# Sheet1.net
KiCad netlist of a schematic drawn in Altium Designer
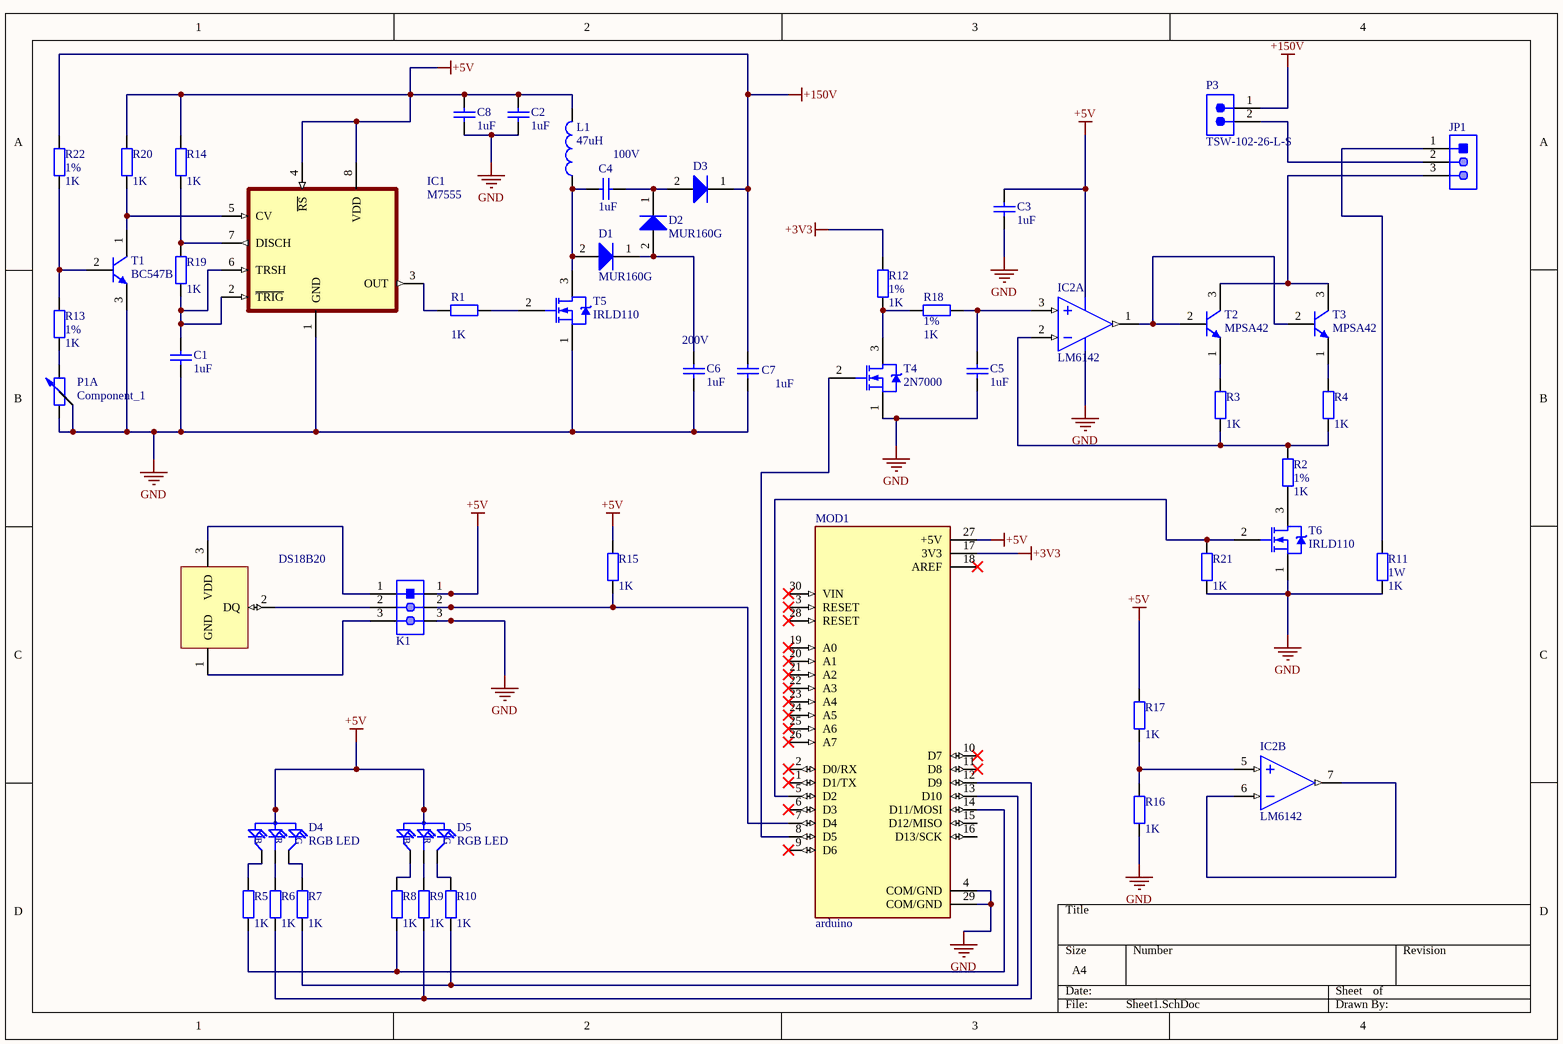
[diagram p0: Sheet1.SchDoc]

(export (version "E")
  (design (tool "Eeschema 10.0.6"))
  (components
    (comp (ref "C1")
      (value "1uF")
      (footprint "RAD-0.3")
      (description "Capacitor")
      (fields (field (name "Comment") "Cap") (field (name "PUBLISHER") "Altium Limited"))
      (libsource (lib "SchemaLIB") (part "Capacitor"))
    )
    (comp (ref "C2")
      (value "1uF")
      (footprint "RAD-0.3")
      (description "Capacitor")
      (fields (field (name "Comment") "Cap") (field (name "PUBLISHER") "Altium Limited"))
      (libsource (lib "SchemaLIB") (part "Capacitor"))
    )
    (comp (ref "C3")
      (value "1uF")
      (footprint "RAD-0.3")
      (description "Capacitor")
      (fields (field (name "Comment") "Cap") (field (name "PUBLISHER") "Altium Limited"))
      (libsource (lib "SchemaLIB") (part "Capacitor"))
    )
    (comp (ref "C4")
      (value "100V")
      (footprint "Ceramic Capacitor")
      (description "Capacitor")
      (fields (field (name "ALTIUM_VALUE") "1uF") (field (name "PUBLISHER") "Altium Limited"))
      (libsource (lib "SchemaLIB") (part "Capacitor"))
    )
    (comp (ref "C5")
      (value "1uF")
      (footprint "RAD-0.3")
      (description "Capacitor")
      (fields (field (name "Comment") "Cap") (field (name "PUBLISHER") "Altium Limited"))
      (libsource (lib "SchemaLIB") (part "Capacitor"))
    )
    (comp (ref "C6")
      (value "200V")
      (footprint "electrolytic capacitor 2.2uf")
      (description "Capacitor")
      (fields (field (name "ALTIUM_VALUE") "1uF") (field (name "PUBLISHER") "Altium Limited"))
      (libsource (lib "Nixie-thermometer_SchemaLIB") (part "C1uF"))
    )
    (comp (ref "C7")
      (value "1uF")
      (footprint "electrolytic capacitor 2.2uf")
      (description "Capacitor")
      (fields (field (name "Comment") "200V") (field (name "PUBLISHER") "Altium Limited"))
      (libsource (lib "Nixie-thermometer_SchemaLIB") (part "C1uF"))
    )
    (comp (ref "C8")
      (value "1uF")
      (footprint "RAD-0.3")
      (description "Capacitor")
      (fields (field (name "Comment") "Cap") (field (name "PUBLISHER") "Altium Limited"))
      (libsource (lib "SchemaLIB") (part "Capacitor"))
    )
    (comp (ref "D1")
      (value "MUR160G")
      (footprint "MUR160G")
      (description "Diode")
      (fields (field (name "MANUFACTURER") "ON Semiconductor"))
      (libsource (lib "SchemaLIB") (part "Diode"))
    )
    (comp (ref "D2")
      (value "MUR160G")
      (footprint "MUR160G")
      (description "Diode")
      (fields (field (name "MANUFACTURER") "ON Semiconductor"))
      (libsource (lib "SchemaLIB") (part "Diode"))
    )
    (comp (ref "D3")
      (value "MUR160G")
      (footprint "MUR160G")
      (description "Diode")
      (fields (field (name "MANUFACTURER") "ON Semiconductor"))
      (libsource (lib "SchemaLIB") (part "Diode"))
    )
    (comp (ref "D4") (value "RGB LED") (description "RGB Led") (libsource (lib "SchemaLIB") (part "RGB LED")))
    (comp (ref "D5") (value "RGB LED") (description "RGB Led") (libsource (lib "SchemaLIB") (part "RGB LED")))
    (comp (ref "DS18B20")
      (value "DS18B20+")
      (footprint "Q3+1")
      (description "IC")
      (fields (field (name "MANUFACTURER") "Maxim"))
      (libsource (lib "SchemaLIB") (part "DS18B20+"))
    )
    (comp (ref "IC1")
      (value "M7555")
      (footprint "M7555")
      (description "IC")
      (fields (field (name "MF") "Renesas Electronics") (field (name "MP") "ICM7555CBAZ"))
      (libsource (lib "SchemaLIB") (part "M7555"))
    )
    (comp (ref "IC2")
      (value "LM6142")
      (footprint "LM6142")
      (description "IC")
      (fields
        (field (name "MANUFACTURER") "TI National Semiconductor")
        (field (name "MANUFACTURER PART NUMBER") "LM6142AIM")
      )
      (libsource (lib "SchemaLIB") (part "LM6412"))
    )
    (comp (ref "JP1")
      (value "22-28-4033")
      (footprint "MOLX-22-28-4033_V")
      (description "Male Header, Pitch 2.54 mm, 1 x 3 Position, Height 8.38 mm, Tail Length 3.18 mm, RoHS, Bulk")
      (fields (field (name "MANUFACTURER") "Molex"))
      (libsource (lib "Altium Content Vault") (part "CN-1P-M-R3"))
    )
    (comp (ref "K1")
      (value "61900319521")
      (footprint "K1")
      (description "Connector")
      (fields (field (name "MANUFACTURER") "Wurth Electronics") (field (name "PUBLISHER") "WurthElektronik"))
      (libsource (lib "Nixie-thermometer_SchemaLIB") (part "K1"))
    )
    (comp (ref "L1")
      (value "47uH")
      (footprint "ELC08D470E")
      (description "Inductor")
      (fields (field (name "PUBLISHER") "Altium Limited"))
      (libsource (lib "SchemaLIB") (part "Inductor"))
    )
    (comp (ref "MOD1")
      (value "arduino")
      (description "Arduino nano")
      (libsource (lib "SchemaLIB") (part "arduino"))
    )
    (comp (ref "P1") (value "Component_1") (libsource (lib "pot") (part "Component_1")))
    (comp (ref "P3")
      (value "TSW-102-26-L-S")
      (footprint "SMTC-TSW-102-26-XX-S")
      (description "0.025\" SQ Post Header, Through-hole, Vertical, -55 to 125 degC, 2.54 mm Pitch, 2-Pin, Male, RoHS")
      (fields (field (name "MANUFACTURER") "Samtec"))
      (libsource (lib "Altium Content Vault") (part "SMTC-TSW-102-X-X-S-X"))
    )
    (comp (ref "R1")
      (value "1K")
      (footprint "Resistor")
      (description "Resistor")
      (fields (field (name "Comment") "1%") (field (name "PUBLISHER") "Altium Limited"))
      (libsource (lib "") (part "Resistor_1"))
    )
    (comp (ref "R2")
      (value "1%")
      (footprint "SMD resistor")
      (description "Resistor")
      (fields (field (name "ALTIUM_VALUE") "1K") (field (name "PUBLISHER") "Altium Limited"))
      (libsource (lib "Miscellaneous Devices") (part "Res2"))
    )
    (comp (ref "R3")
      (value "1K")
      (footprint "SMD resistor")
      (description "Resistor")
      (fields (field (name "Comment") "Res2") (field (name "PUBLISHER") "Altium Limited"))
      (libsource (lib "Miscellaneous Devices") (part "Res2"))
    )
    (comp (ref "R4")
      (value "1K")
      (footprint "SMD resistor")
      (description "Resistor")
      (fields (field (name "Comment") "Res2") (field (name "PUBLISHER") "Altium Limited"))
      (libsource (lib "Miscellaneous Devices") (part "Res2"))
    )
    (comp (ref "R5")
      (value "1K")
      (footprint "Resistor")
      (description "Resistor")
      (fields (field (name "Comment") "Res2") (field (name "PUBLISHER") "Altium Limited"))
      (libsource (lib "Miscellaneous Devices") (part "Res2"))
    )
    (comp (ref "R6")
      (value "1K")
      (footprint "Resistor")
      (description "Resistor")
      (fields (field (name "Comment") "Res2") (field (name "PUBLISHER") "Altium Limited"))
      (libsource (lib "Miscellaneous Devices") (part "Res2"))
    )
    (comp (ref "R7")
      (value "1K")
      (footprint "Resistor")
      (description "Resistor")
      (fields (field (name "Comment") "Res2") (field (name "PUBLISHER") "Altium Limited"))
      (libsource (lib "Miscellaneous Devices") (part "Res2"))
    )
    (comp (ref "R8")
      (value "1K")
      (footprint "Resistor")
      (description "Resistor")
      (fields (field (name "Comment") "Res2") (field (name "PUBLISHER") "Altium Limited"))
      (libsource (lib "Miscellaneous Devices") (part "Res2"))
    )
    (comp (ref "R9")
      (value "1K")
      (footprint "Resistor")
      (description "Resistor")
      (fields (field (name "Comment") "Res2") (field (name "PUBLISHER") "Altium Limited"))
      (libsource (lib "Miscellaneous Devices") (part "Res2"))
    )
    (comp (ref "R10")
      (value "1K")
      (footprint "Resistor")
      (description "Resistor")
      (fields (field (name "Comment") "Res2") (field (name "PUBLISHER") "Altium Limited"))
      (libsource (lib "Miscellaneous Devices") (part "Res2"))
    )
    (comp (ref "R11")
      (value "1W")
      (footprint "RESISTOR 1W")
      (description "Resistor")
      (fields (field (name "ALTIUM_VALUE") "1K") (field (name "PUBLISHER") "Altium Limited"))
      (libsource (lib "SchemaLIB") (part "Resistor"))
    )
    (comp (ref "R12")
      (value "1%")
      (footprint "SMD resistor")
      (description "Resistor")
      (fields (field (name "ALTIUM_VALUE") "1K") (field (name "PUBLISHER") "Altium Limited"))
      (libsource (lib "SchemaLIB") (part "Resistor"))
    )
    (comp (ref "R13")
      (value "1%")
      (footprint "Resistor")
      (description "Resistor")
      (fields (field (name "ALTIUM_VALUE") "1K") (field (name "PUBLISHER") "Altium Limited"))
      (libsource (lib "Miscellaneous Devices") (part "Res2"))
    )
    (comp (ref "R14")
      (value "1K")
      (footprint "Resistor")
      (description "Resistor")
      (fields (field (name "Comment") "Res2") (field (name "PUBLISHER") "Altium Limited"))
      (libsource (lib "Miscellaneous Devices") (part "Res2"))
    )
    (comp (ref "R15")
      (value "1K")
      (footprint "Resistor")
      (description "Resistor")
      (fields (field (name "Comment") "Res2") (field (name "PUBLISHER") "Altium Limited"))
      (libsource (lib "Miscellaneous Devices") (part "Res2"))
    )
    (comp (ref "R16")
      (value "1K")
      (footprint "SMD resistor")
      (description "Resistor")
      (fields (field (name "Comment") "1%") (field (name "PUBLISHER") "Altium Limited"))
      (libsource (lib "SchemaLIB") (part "Resistor"))
    )
    (comp (ref "R17")
      (value "1K")
      (footprint "SMD resistor")
      (description "Resistor")
      (fields (field (name "Comment") "1%") (field (name "PUBLISHER") "Altium Limited"))
      (libsource (lib "SchemaLIB") (part "Resistor"))
    )
    (comp (ref "R18")
      (value "1%")
      (footprint "SMD resistor")
      (description "Resistor")
      (fields (field (name "ALTIUM_VALUE") "1K") (field (name "PUBLISHER") "Altium Limited"))
      (libsource (lib "") (part "Resistor_1"))
    )
    (comp (ref "R19")
      (value "1K")
      (footprint "Resistor")
      (description "Resistor")
      (fields (field (name "Comment") "Res2") (field (name "PUBLISHER") "Altium Limited"))
      (libsource (lib "Miscellaneous Devices") (part "Res2"))
    )
    (comp (ref "R20")
      (value "1K")
      (footprint "Resistor")
      (description "Resistor")
      (fields (field (name "Comment") "Res2") (field (name "PUBLISHER") "Altium Limited"))
      (libsource (lib "Miscellaneous Devices") (part "Res2"))
    )
    (comp (ref "R21")
      (value "1K")
      (footprint "SMD resistor")
      (description "Resistor")
      (fields (field (name "Comment") "1%") (field (name "PUBLISHER") "Altium Limited"))
      (libsource (lib "SchemaLIB") (part "Resistor"))
    )
    (comp (ref "R22")
      (value "1%")
      (footprint "Resistor")
      (description "Resistor")
      (fields (field (name "ALTIUM_VALUE") "1K") (field (name "PUBLISHER") "Altium Limited"))
      (libsource (lib "SchemaLIB") (part "Resistor"))
    )
    (comp (ref "T1")
      (value "BC547B")
      (footprint "BC547B")
      (description "Transistor")
      (fields (field (name "MANUFACTURER") "ON Semiconductor / Fairchild"))
      (libsource (lib "SchemaLIB") (part "BC547B"))
    )
    (comp (ref "T2")
      (value "MPSA42")
      (footprint "BC547B")
      (description "Transistor")
      (fields (field (name "MANUFACTURER") "ON Semiconductor / Fairchild"))
      (libsource (lib "SchemaLIB") (part "MPSA42"))
    )
    (comp (ref "T3")
      (value "MPSA42")
      (footprint "BC547B")
      (description "Transistor")
      (fields (field (name "MANUFACTURER") "ON Semiconductor / Fairchild"))
      (libsource (lib "SchemaLIB") (part "MPSA42"))
    )
    (comp (ref "T4")
      (value "2N7000")
      (footprint "BC547B")
      (description "Transistor")
      (fields (field (name "MANUFACTURER") "ON Semiconductor / Fairchild"))
      (libsource (lib "SchemaLIB") (part "IC2N7000"))
    )
    (comp (ref "T5")
      (value "IRLD110")
      (description "Transistor")
      (libsource (lib "SchemaLIB") (part "IRLD110"))
    )
    (comp (ref "T6")
      (value "IRLD110")
      (description "Transistor")
      (libsource (lib "SchemaLIB") (part "IRLD110"))
    )
  )
  (nets
    (net (code "1") (name "+3V3") (class "Default")
      (node (ref "MOD1") (pin "17") (pinfunction "3V3_17") (pintype "power_in"))
      (node (ref "R12") (pin "2") (pinfunction "2_2") (pintype "passive"))
    )
    (net (code "2") (name "+5V") (class "Default")
      (node (ref "C2") (pin "2") (pinfunction "2_2") (pintype "passive"))
      (node (ref "C3") (pin "2") (pinfunction "2_2") (pintype "passive"))
      (node (ref "C8") (pin "2") (pinfunction "2_2") (pintype "passive"))
      (node (ref "D4") (pin "C") (pinfunction "POS_C") (pintype "bidirectional"))
      (node (ref "D5") (pin "C") (pinfunction "POS_C") (pintype "bidirectional"))
      (node (ref "IC1") (pin "4") (pinfunction "~{RS}_4") (pintype "input"))
      (node (ref "IC1") (pin "8") (pinfunction "VDD_8") (pintype "power_in"))
      (node (ref "K1") (pin "1") (pinfunction "1_1") (pintype "passive"))
      (node (ref "L1") (pin "2") (pinfunction "2_2") (pintype "passive"))
      (node (ref "MOD1") (pin "27") (pinfunction "+5V_27") (pintype "power_in"))
      (node (ref "R14") (pin "2") (pinfunction "2_2") (pintype "passive"))
      (node (ref "R15") (pin "2") (pinfunction "2_2") (pintype "passive"))
      (node (ref "R17") (pin "2") (pinfunction "2_2") (pintype "passive"))
      (node (ref "R20") (pin "2") (pinfunction "2_2") (pintype "passive"))
    )
    (net (code "3") (name "+150V") (class "Default")
      (node (ref "C7") (pin "2") (pinfunction "2_2") (pintype "passive"))
      (node (ref "D3") (pin "1") (pinfunction "K_1") (pintype "passive"))
      (node (ref "P3") (pin "1") (pinfunction "1_1") (pintype "passive"))
      (node (ref "R22") (pin "2") (pinfunction "2_2") (pintype "passive"))
    )
    (net (code "4") (name "GND") (class "Default")
      (node (ref "C1") (pin "1") (pinfunction "1_1") (pintype "passive"))
      (node (ref "C2") (pin "1") (pinfunction "1_1") (pintype "passive"))
      (node (ref "C3") (pin "1") (pinfunction "1_1") (pintype "passive"))
      (node (ref "C5") (pin "1") (pinfunction "1_1") (pintype "passive"))
      (node (ref "C6") (pin "1") (pinfunction "1_1") (pintype "passive"))
      (node (ref "C7") (pin "1") (pinfunction "1_1") (pintype "passive"))
      (node (ref "C8") (pin "1") (pinfunction "1_1") (pintype "passive"))
      (node (ref "IC1") (pin "1") (pinfunction "GND_1") (pintype "passive"))
      (node (ref "K1") (pin "3") (pinfunction "3_3") (pintype "passive"))
      (node (ref "MOD1") (pin "29") (pinfunction "COM/GND_29") (pintype "power_in"))
      (node (ref "MOD1") (pin "4") (pinfunction "COM/GND_4") (pintype "power_in"))
      (node (ref "P1") (pin "1") (pinfunction "1_1") (pintype "passive"))
      (node (ref "P1") (pin "3") (pinfunction "3_3") (pintype "passive"))
      (node (ref "R11") (pin "1") (pinfunction "1_1") (pintype "passive"))
      (node (ref "R16") (pin "1") (pinfunction "1_1") (pintype "passive"))
      (node (ref "R21") (pin "1") (pinfunction "1_1") (pintype "passive"))
      (node (ref "T1") (pin "3") (pinfunction "E_3") (pintype "passive"))
      (node (ref "T4") (pin "1") (pinfunction "S_1") (pintype "passive"))
      (node (ref "T5") (pin "1") (pinfunction "S_1") (pintype "passive"))
      (node (ref "T6") (pin "1") (pinfunction "S_1") (pintype "passive"))
    )
    (net (code "5") (name "Net-(D1-A)") (class "Default")
      (node (ref "C4") (pin "2") (pinfunction "2_2") (pintype "passive"))
      (node (ref "D1") (pin "2") (pinfunction "A_2") (pintype "passive"))
      (node (ref "L1") (pin "1") (pinfunction "1_1") (pintype "passive"))
      (node (ref "T5") (pin "3") (pinfunction "D_3") (pintype "passive"))
    )
    (net (code "6") (name "Net-(D1-K)") (class "Default")
      (node (ref "C6") (pin "2") (pinfunction "2_2") (pintype "passive"))
      (node (ref "D1") (pin "1") (pinfunction "K_1") (pintype "passive"))
      (node (ref "D2") (pin "2") (pinfunction "A_2") (pintype "passive"))
    )
    (net (code "7") (name "Net-(D2-K)") (class "Default")
      (node (ref "C4") (pin "1") (pinfunction "1_1") (pintype "passive"))
      (node (ref "D2") (pin "1") (pinfunction "K_1") (pintype "passive"))
      (node (ref "D3") (pin "2") (pinfunction "A_2") (pintype "passive"))
    )
    (net (code "8") (name "Net-(D4-PadB)") (class "Default")
      (node (ref "D4") (pin "B") (pinfunction "B_B") (pintype "bidirectional"))
      (node (ref "R5") (pin "2") (pinfunction "2_2") (pintype "passive"))
    )
    (net (code "9") (name "Net-(D4-PadG)") (class "Default")
      (node (ref "D4") (pin "G") (pinfunction "G_G") (pintype "bidirectional"))
      (node (ref "R7") (pin "2") (pinfunction "2_2") (pintype "passive"))
    )
    (net (code "10") (name "Net-(D4-PadR)") (class "Default")
      (node (ref "D4") (pin "R") (pinfunction "R_R") (pintype "bidirectional"))
      (node (ref "R6") (pin "2") (pinfunction "2_2") (pintype "passive"))
    )
    (net (code "11") (name "Net-(D5-PadB)") (class "Default")
      (node (ref "D5") (pin "B") (pinfunction "B_B") (pintype "bidirectional"))
      (node (ref "R8") (pin "2") (pinfunction "2_2") (pintype "passive"))
    )
    (net (code "12") (name "Net-(D5-PadG)") (class "Default")
      (node (ref "D5") (pin "G") (pinfunction "G_G") (pintype "bidirectional"))
      (node (ref "R10") (pin "2") (pinfunction "2_2") (pintype "passive"))
    )
    (net (code "13") (name "Net-(D5-PadR)") (class "Default")
      (node (ref "D5") (pin "R") (pinfunction "R_R") (pintype "bidirectional"))
      (node (ref "R9") (pin "2") (pinfunction "2_2") (pintype "passive"))
    )
    (net (code "14") (name "Net-(DS18B20-DQ)") (class "Default")
      (node (ref "DS18B20") (pin "2") (pinfunction "DQ_2") (pintype "bidirectional"))
      (node (ref "K1") (pin "2") (pinfunction "2_2") (pintype "passive"))
    )
    (net (code "15") (name "Net-(DS18B20-GND)") (class "Default")
      (node (ref "DS18B20") (pin "1") (pinfunction "GND_1") (pintype "power_in"))
      (node (ref "K1") (pin "3") (pinfunction "3_3") (pintype "passive"))
    )
    (net (code "16") (name "Net-(DS18B20-VDD)") (class "Default")
      (node (ref "DS18B20") (pin "3") (pinfunction "VDD_3") (pintype "power_in"))
      (node (ref "K1") (pin "1") (pinfunction "1_1") (pintype "passive"))
    )
    (net (code "17") (name "Net-(IC1-CV)") (class "Default")
      (node (ref "IC1") (pin "5") (pinfunction "CV_5") (pintype "input"))
      (node (ref "R20") (pin "1") (pinfunction "1_1") (pintype "passive"))
      (node (ref "T1") (pin "1") (pinfunction "C_1") (pintype "passive"))
    )
    (net (code "18") (name "Net-(IC1-DISCH)") (class "Default")
      (node (ref "IC1") (pin "7") (pinfunction "DISCH_7") (pintype "output"))
      (node (ref "R14") (pin "1") (pinfunction "1_1") (pintype "passive"))
      (node (ref "R19") (pin "2") (pinfunction "2_2") (pintype "passive"))
    )
    (net (code "19") (name "Net-(IC1-OUT)") (class "Default")
      (node (ref "IC1") (pin "3") (pinfunction "OUT_3") (pintype "output"))
      (node (ref "R1") (pin "1") (pinfunction "1_1") (pintype "passive"))
    )
    (net (code "20") (name "Net-(IC1-TRSH)") (class "Default")
      (node (ref "C1") (pin "2") (pinfunction "2_2") (pintype "passive"))
      (node (ref "IC1") (pin "2") (pinfunction "~{TRIG}_2") (pintype "input"))
      (node (ref "IC1") (pin "6") (pinfunction "TRSH_6") (pintype "input"))
      (node (ref "R19") (pin "1") (pinfunction "1_1") (pintype "passive"))
    )
    (net (code "21") (name "Net-(IC2A-INA+)") (class "Default")
      (node (ref "C5") (pin "2") (pinfunction "2_2") (pintype "passive"))
      (node (ref "IC2") (pin "3") (pinfunction "INA+_3") (pintype "input"))
      (node (ref "R18") (pin "2") (pinfunction "2_2") (pintype "passive"))
    )
    (net (code "22") (name "Net-(IC2A-INA-)") (class "Default")
      (node (ref "IC2") (pin "2") (pinfunction "INA-_2") (pintype "input"))
      (node (ref "R2") (pin "2") (pinfunction "2_2") (pintype "passive"))
      (node (ref "R3") (pin "1") (pinfunction "1_1") (pintype "passive"))
      (node (ref "R4") (pin "1") (pinfunction "1_1") (pintype "passive"))
    )
    (net (code "23") (name "Net-(IC2A-OUTA)") (class "Default")
      (node (ref "IC2") (pin "1") (pinfunction "OUTA_1") (pintype "output"))
      (node (ref "T2") (pin "2") (pinfunction "B_2") (pintype "passive"))
      (node (ref "T3") (pin "2") (pinfunction "B_2") (pintype "passive"))
    )
    (net (code "24") (name "Net-(IC2B-INB+)") (class "Default")
      (node (ref "IC2") (pin "5") (pinfunction "INB+_5") (pintype "input"))
      (node (ref "R16") (pin "2") (pinfunction "2_2") (pintype "passive"))
      (node (ref "R17") (pin "1") (pinfunction "1_1") (pintype "passive"))
    )
    (net (code "25") (name "Net-(IC2B-INB-)") (class "Default")
      (node (ref "IC2") (pin "6") (pinfunction "INB-_6") (pintype "input"))
      (node (ref "IC2") (pin "7") (pinfunction "OUTB_7") (pintype "output"))
    )
    (net (code "26") (name "Net-(JP1-Pad1)") (class "Default")
      (node (ref "JP1") (pin "1") (pinfunction "1_1") (pintype "passive"))
      (node (ref "R11") (pin "2") (pinfunction "2_2") (pintype "passive"))
    )
    (net (code "27") (name "Net-(JP1-Pad2)") (class "Default")
      (node (ref "JP1") (pin "2") (pinfunction "2_2") (pintype "passive"))
      (node (ref "P3") (pin "2") (pinfunction "2_2") (pintype "passive"))
    )
    (net (code "28") (name "Net-(MOD1-D2)") (class "Default")
      (node (ref "MOD1") (pin "5") (pinfunction "D2_5") (pintype "bidirectional"))
      (node (ref "R21") (pin "2") (pinfunction "2_2") (pintype "passive"))
      (node (ref "T6") (pin "2") (pinfunction "G_2") (pintype "passive"))
    )
    (net (code "29") (name "Net-(MOD1-D4)") (class "Default")
      (node (ref "K1") (pin "2") (pinfunction "2_2") (pintype "passive"))
      (node (ref "MOD1") (pin "7") (pinfunction "D4_7") (pintype "bidirectional"))
      (node (ref "R15") (pin "1") (pinfunction "1_1") (pintype "passive"))
    )
    (net (code "30") (name "Net-(MOD1-D5)") (class "Default")
      (node (ref "MOD1") (pin "8") (pinfunction "D5_8") (pintype "bidirectional"))
      (node (ref "T4") (pin "2") (pinfunction "G_2") (pintype "passive"))
    )
    (net (code "31") (name "Net-(MOD1-D9)") (class "Default")
      (node (ref "MOD1") (pin "12") (pinfunction "D9_12") (pintype "bidirectional"))
      (node (ref "R6") (pin "1") (pinfunction "1_1") (pintype "passive"))
      (node (ref "R9") (pin "1") (pinfunction "1_1") (pintype "passive"))
    )
    (net (code "32") (name "Net-(MOD1-D10)") (class "Default")
      (node (ref "MOD1") (pin "13") (pinfunction "D10_13") (pintype "bidirectional"))
      (node (ref "R10") (pin "1") (pinfunction "1_1") (pintype "passive"))
      (node (ref "R7") (pin "1") (pinfunction "1_1") (pintype "passive"))
    )
    (net (code "33") (name "Net-(MOD1-D11{slash}MOSI)") (class "Default")
      (node (ref "MOD1") (pin "14") (pinfunction "D11/MOSI_14") (pintype "bidirectional"))
      (node (ref "R5") (pin "1") (pinfunction "1_1") (pintype "passive"))
      (node (ref "R8") (pin "1") (pinfunction "1_1") (pintype "passive"))
    )
    (net (code "34") (name "Net-(P1-Pad2)") (class "Default")
      (node (ref "P1") (pin "2") (pinfunction "2_2") (pintype "passive"))
      (node (ref "R13") (pin "1") (pinfunction "1_1") (pintype "passive"))
    )
    (net (code "35") (name "Net-(T1-B)") (class "Default")
      (node (ref "R13") (pin "2") (pinfunction "2_2") (pintype "passive"))
      (node (ref "R22") (pin "1") (pinfunction "1_1") (pintype "passive"))
      (node (ref "T1") (pin "2") (pinfunction "B_2") (pintype "passive"))
    )
    (net (code "36") (name "Net-(T2-C)") (class "Default")
      (node (ref "JP1") (pin "3") (pinfunction "3_3") (pintype "passive"))
      (node (ref "T2") (pin "3") (pinfunction "C_3") (pintype "passive"))
      (node (ref "T3") (pin "3") (pinfunction "C_3") (pintype "passive"))
    )
    (net (code "37") (name "Net-(T2-E)") (class "Default")
      (node (ref "R3") (pin "2") (pinfunction "2_2") (pintype "passive"))
      (node (ref "T2") (pin "1") (pinfunction "E_1") (pintype "passive"))
    )
    (net (code "38") (name "Net-(T3-E)") (class "Default")
      (node (ref "R4") (pin "2") (pinfunction "2_2") (pintype "passive"))
      (node (ref "T3") (pin "1") (pinfunction "E_1") (pintype "passive"))
    )
    (net (code "39") (name "Net-(T4-D)") (class "Default")
      (node (ref "R12") (pin "1") (pinfunction "1_1") (pintype "passive"))
      (node (ref "R18") (pin "1") (pinfunction "1_1") (pintype "passive"))
      (node (ref "T4") (pin "3") (pinfunction "D_3") (pintype "passive"))
    )
    (net (code "40") (name "Net-(T5-G)") (class "Default")
      (node (ref "R1") (pin "2") (pinfunction "2_2") (pintype "passive"))
      (node (ref "T5") (pin "2") (pinfunction "G_2") (pintype "passive"))
    )
    (net (code "41") (name "Net-(T6-D)") (class "Default")
      (node (ref "R2") (pin "1") (pinfunction "1_1") (pintype "passive"))
      (node (ref "T6") (pin "3") (pinfunction "D_3") (pintype "passive"))
    )
    (net (code "42") (name "unconnected-(MOD1-A0-Pad19)") (class "Default")
      (node (ref "MOD1") (pin "19") (pinfunction "A0_19") (pintype "input+no_connect"))
    )
    (net (code "43") (name "unconnected-(MOD1-A1-Pad20)") (class "Default")
      (node (ref "MOD1") (pin "20") (pinfunction "A1_20") (pintype "input+no_connect"))
    )
    (net (code "44") (name "unconnected-(MOD1-A2-Pad21)") (class "Default")
      (node (ref "MOD1") (pin "21") (pinfunction "A2_21") (pintype "input+no_connect"))
    )
    (net (code "45") (name "unconnected-(MOD1-A3-Pad22)") (class "Default")
      (node (ref "MOD1") (pin "22") (pinfunction "A3_22") (pintype "input+no_connect"))
    )
    (net (code "46") (name "unconnected-(MOD1-A4-Pad23)") (class "Default")
      (node (ref "MOD1") (pin "23") (pinfunction "A4_23") (pintype "input+no_connect"))
    )
    (net (code "47") (name "unconnected-(MOD1-A5-Pad24)") (class "Default")
      (node (ref "MOD1") (pin "24") (pinfunction "A5_24") (pintype "input+no_connect"))
    )
    (net (code "48") (name "unconnected-(MOD1-A6-Pad25)") (class "Default")
      (node (ref "MOD1") (pin "25") (pinfunction "A6_25") (pintype "input+no_connect"))
    )
    (net (code "49") (name "unconnected-(MOD1-A7-Pad26)") (class "Default")
      (node (ref "MOD1") (pin "26") (pinfunction "A7_26") (pintype "input+no_connect"))
    )
    (net (code "50") (name "unconnected-(MOD1-AREF-Pad18)") (class "Default")
      (node (ref "MOD1") (pin "18") (pinfunction "AREF_18") (pintype "power_in+no_connect"))
    )
    (net (code "51") (name "unconnected-(MOD1-D0{slash}RX-Pad2)") (class "Default")
      (node (ref "MOD1") (pin "2") (pinfunction "D0/RX_2") (pintype "bidirectional+no_connect"))
    )
    (net (code "52") (name "unconnected-(MOD1-D1{slash}TX-Pad1)") (class "Default")
      (node (ref "MOD1") (pin "1") (pinfunction "D1/TX_1") (pintype "bidirectional+no_connect"))
    )
    (net (code "53") (name "unconnected-(MOD1-D3-Pad6)") (class "Default")
      (node (ref "MOD1") (pin "6") (pinfunction "D3_6") (pintype "bidirectional+no_connect"))
    )
    (net (code "54") (name "unconnected-(MOD1-D6-Pad9)") (class "Default")
      (node (ref "MOD1") (pin "9") (pinfunction "D6_9") (pintype "bidirectional+no_connect"))
    )
    (net (code "55") (name "unconnected-(MOD1-D7-Pad10)") (class "Default")
      (node (ref "MOD1") (pin "10") (pinfunction "D7_10") (pintype "bidirectional+no_connect"))
    )
    (net (code "56") (name "unconnected-(MOD1-D8-Pad11)") (class "Default")
      (node (ref "MOD1") (pin "11") (pinfunction "D8_11") (pintype "bidirectional+no_connect"))
    )
    (net (code "57") (name "unconnected-(MOD1-D12{slash}MISO-Pad15)") (class "Default")
      (node (ref "MOD1") (pin "15") (pinfunction "D12/MISO_15") (pintype "bidirectional"))
    )
    (net (code "58") (name "unconnected-(MOD1-D13{slash}SCK-Pad16)") (class "Default")
      (node (ref "MOD1") (pin "16") (pinfunction "D13/SCK_16") (pintype "bidirectional"))
    )
    (net (code "59") (name "unconnected-(MOD1-RESET-Pad3)") (class "Default")
      (node (ref "MOD1") (pin "3") (pinfunction "RESET_3") (pintype "input+no_connect"))
    )
    (net (code "60") (name "unconnected-(MOD1-RESET-Pad28)") (class "Default")
      (node (ref "MOD1") (pin "28") (pinfunction "RESET_28") (pintype "input+no_connect"))
    )
    (net (code "61") (name "unconnected-(MOD1-VIN-Pad30)") (class "Default")
      (node (ref "MOD1") (pin "30") (pinfunction "VIN_30") (pintype "input+no_connect"))
    )
  )
)
